# schematic_revision_1.net
KiCad netlist of a schematic drawn in EAGLE
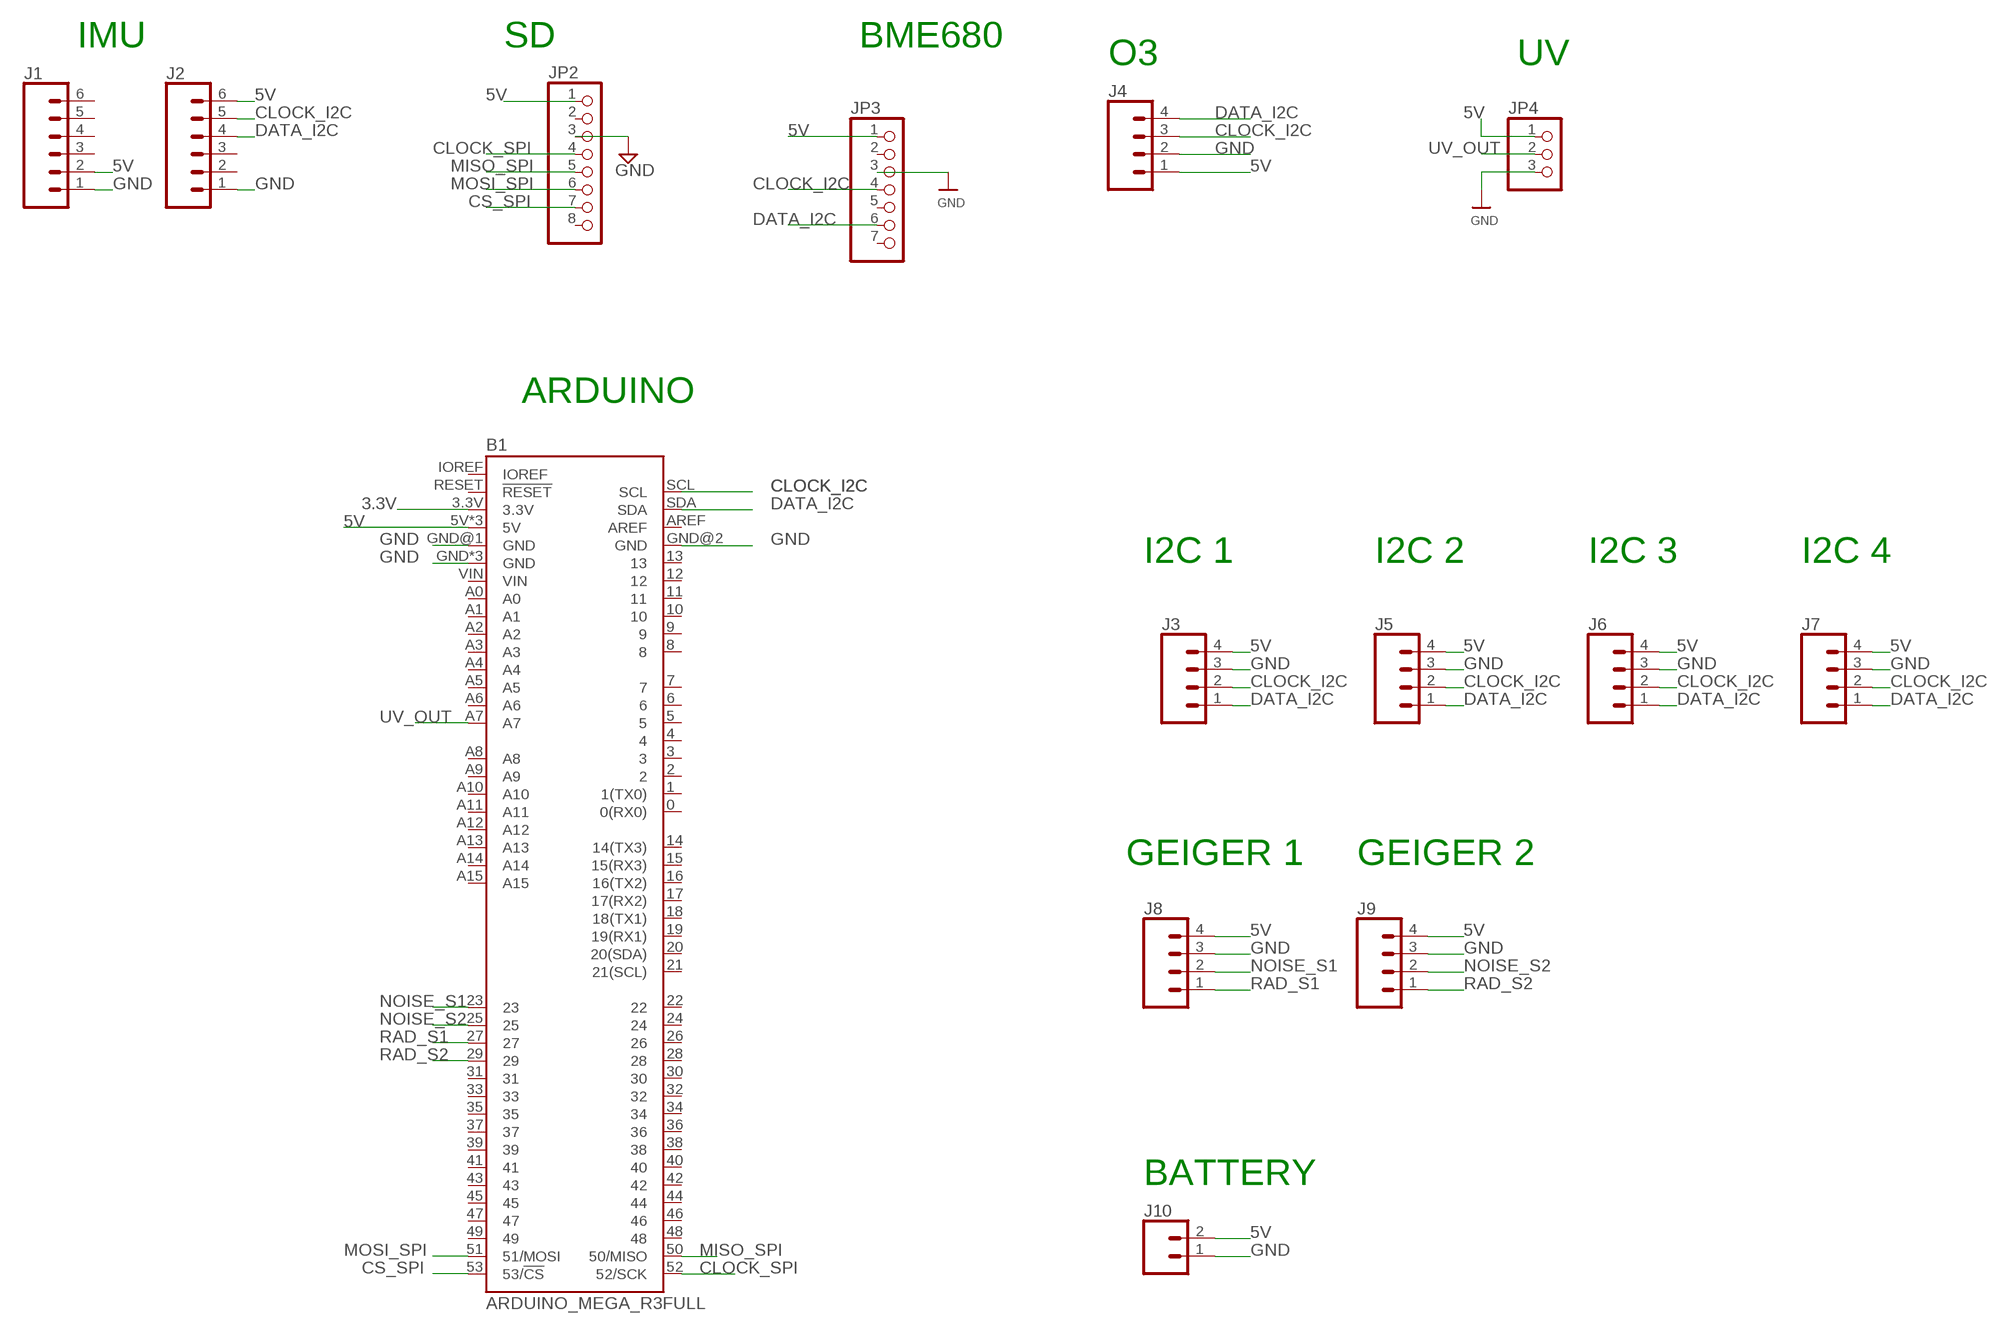
[diagram p0: schematic, sheet 1, part 1 of 2]
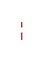
[diagram p1: schematic, sheet 1, part 2 of 2]

(export (version "E")
  (design (tool "Eeschema 10.0.6"))
  (components
    (comp (ref "B1")
      (value "ARDUINO_MEGA_R3FULL")
      (footprint "eagle-import:ARDUINO_MEGA_NO_SILK")
      (libsource (lib "eagle-import") (part "ARDUINO_MEGA_R3FULL"))
    )
    (comp (ref "J1")
      (value "CONN_06NO_SILK_NO_POP")
      (footprint "eagle-import:1X06_NO_SILK")
      (libsource (lib "eagle-import") (part "CONN_06NO_SILK_NO_POP"))
    )
    (comp (ref "J2")
      (value "CONN_06NO_SILK_NO_POP")
      (footprint "eagle-import:1X06_NO_SILK")
      (libsource (lib "eagle-import") (part "CONN_06NO_SILK_NO_POP"))
    )
    (comp (ref "J3")
      (value "CONN_04PTH")
      (footprint "eagle-import:1X04")
      (libsource (lib "eagle-import") (part "CONN_04PTH"))
    )
    (comp (ref "J4")
      (value "CONN_04LOCK")
      (footprint "eagle-import:1X04_LOCK")
      (libsource (lib "eagle-import") (part "CONN_04LOCK"))
    )
    (comp (ref "J5")
      (value "CONN_04PTH")
      (footprint "eagle-import:1X04")
      (libsource (lib "eagle-import") (part "CONN_04PTH"))
    )
    (comp (ref "J6")
      (value "CONN_04PTH")
      (footprint "eagle-import:1X04")
      (libsource (lib "eagle-import") (part "CONN_04PTH"))
    )
    (comp (ref "J7")
      (value "CONN_04PTH")
      (footprint "eagle-import:1X04")
      (libsource (lib "eagle-import") (part "CONN_04PTH"))
    )
    (comp (ref "J8")
      (value "CONN_04PTH")
      (footprint "eagle-import:1X04")
      (libsource (lib "eagle-import") (part "CONN_04PTH"))
    )
    (comp (ref "J9")
      (value "CONN_04PTH")
      (footprint "eagle-import:1X04")
      (libsource (lib "eagle-import") (part "CONN_04PTH"))
    )
    (comp (ref "J10")
      (value "CONN_02")
      (footprint "eagle-import:1X02")
      (libsource (lib "eagle-import") (part "CONN_02"))
    )
    (comp (ref "JP2")
      (value "PINHD-1X8BIG")
      (footprint "eagle-import:1X08-BIG")
      (libsource (lib "eagle-import") (part "PINHD-1X8BIG"))
    )
    (comp (ref "JP3")
      (value "HEADER-1X770MIL")
      (footprint "eagle-import:1X07_ROUND_70")
      (libsource (lib "eagle-import") (part "HEADER-1X770MIL"))
    )
    (comp (ref "JP4")
      (value "PINHD-1X3CB")
      (footprint "eagle-import:1X03-CLEANBIG")
      (libsource (lib "eagle-import") (part "PINHD-1X3CB"))
    )
  )
  (nets
    (net (code "1") (name "/3.3V") (class "Default")
      (node (ref "B1") (pin "3.3V") (pinfunction "3.3V_3.3V") (pintype "bidirectional"))
    )
    (net (code "2") (name "/5V") (class "Default")
      (node (ref "B1") (pin "5V") (pinfunction "5V_5V") (pintype "bidirectional"))
      (node (ref "B1") (pin "5V@1") (pinfunction "5V_5V@1") (pintype "bidirectional"))
      (node (ref "B1") (pin "5V@2") (pinfunction "5V_5V@2") (pintype "bidirectional"))
      (node (ref "J1") (pin "2") (pinfunction "2_2") (pintype "passive"))
      (node (ref "J10") (pin "2") (pinfunction "2_2") (pintype "passive"))
      (node (ref "J2") (pin "6") (pinfunction "6_6") (pintype "passive"))
      (node (ref "J3") (pin "4") (pinfunction "4_4") (pintype "passive"))
      (node (ref "J4") (pin "1") (pinfunction "1_1") (pintype "passive"))
      (node (ref "J5") (pin "4") (pinfunction "4_4") (pintype "passive"))
      (node (ref "J6") (pin "4") (pinfunction "4_4") (pintype "passive"))
      (node (ref "J7") (pin "4") (pinfunction "4_4") (pintype "passive"))
      (node (ref "J8") (pin "4") (pinfunction "4_4") (pintype "passive"))
      (node (ref "J9") (pin "4") (pinfunction "4_4") (pintype "passive"))
      (node (ref "JP2") (pin "1") (pinfunction "1_1") (pintype "passive"))
      (node (ref "JP3") (pin "1") (pinfunction "1_1") (pintype "passive"))
      (node (ref "JP4") (pin "1") (pinfunction "1_1") (pintype "passive"))
    )
    (net (code "3") (name "/CLOCK_I2C") (class "Default")
      (node (ref "B1") (pin "SCL") (pinfunction "SCL_SCL") (pintype "bidirectional"))
      (node (ref "J2") (pin "5") (pinfunction "5_5") (pintype "passive"))
      (node (ref "J3") (pin "2") (pinfunction "2_2") (pintype "passive"))
      (node (ref "J4") (pin "3") (pinfunction "3_3") (pintype "passive"))
      (node (ref "J5") (pin "2") (pinfunction "2_2") (pintype "passive"))
      (node (ref "J6") (pin "2") (pinfunction "2_2") (pintype "passive"))
      (node (ref "J7") (pin "2") (pinfunction "2_2") (pintype "passive"))
      (node (ref "JP3") (pin "4") (pinfunction "4_4") (pintype "passive"))
    )
    (net (code "4") (name "/CLOCK_SPI") (class "Default")
      (node (ref "B1") (pin "52") (pinfunction "52/SCK_52") (pintype "bidirectional"))
      (node (ref "JP2") (pin "4") (pinfunction "4_4") (pintype "passive"))
    )
    (net (code "5") (name "/CS_SPI") (class "Default")
      (node (ref "B1") (pin "53") (pinfunction "53/~{CS}_53") (pintype "bidirectional"))
      (node (ref "JP2") (pin "7") (pinfunction "7_7") (pintype "passive"))
    )
    (net (code "6") (name "/DATA_I2C") (class "Default")
      (node (ref "B1") (pin "SDA") (pinfunction "SDA_SDA") (pintype "bidirectional"))
      (node (ref "J2") (pin "4") (pinfunction "4_4") (pintype "passive"))
      (node (ref "J3") (pin "1") (pinfunction "1_1") (pintype "passive"))
      (node (ref "J4") (pin "4") (pinfunction "4_4") (pintype "passive"))
      (node (ref "J5") (pin "1") (pinfunction "1_1") (pintype "passive"))
      (node (ref "J6") (pin "1") (pinfunction "1_1") (pintype "passive"))
      (node (ref "J7") (pin "1") (pinfunction "1_1") (pintype "passive"))
      (node (ref "JP3") (pin "6") (pinfunction "6_6") (pintype "passive"))
    )
    (net (code "7") (name "/MISO_SPI") (class "Default")
      (node (ref "B1") (pin "50") (pinfunction "50/MISO_50") (pintype "bidirectional"))
      (node (ref "JP2") (pin "5") (pinfunction "5_5") (pintype "passive"))
    )
    (net (code "8") (name "/MOSI_SPI") (class "Default")
      (node (ref "B1") (pin "51") (pinfunction "51/MOSI_51") (pintype "bidirectional"))
      (node (ref "JP2") (pin "6") (pinfunction "6_6") (pintype "passive"))
    )
    (net (code "9") (name "/NOISE_S1") (class "Default")
      (node (ref "B1") (pin "23") (pinfunction "23_23") (pintype "bidirectional"))
      (node (ref "J8") (pin "2") (pinfunction "2_2") (pintype "passive"))
    )
    (net (code "10") (name "/NOISE_S2") (class "Default")
      (node (ref "B1") (pin "25") (pinfunction "25_25") (pintype "bidirectional"))
      (node (ref "J9") (pin "2") (pinfunction "2_2") (pintype "passive"))
    )
    (net (code "11") (name "/RAD_S1") (class "Default")
      (node (ref "B1") (pin "27") (pinfunction "27_27") (pintype "bidirectional"))
      (node (ref "J8") (pin "1") (pinfunction "1_1") (pintype "passive"))
    )
    (net (code "12") (name "/RAD_S2") (class "Default")
      (node (ref "B1") (pin "29") (pinfunction "29_29") (pintype "bidirectional"))
      (node (ref "J9") (pin "1") (pinfunction "1_1") (pintype "passive"))
    )
    (net (code "13") (name "/UV_OUT") (class "Default")
      (node (ref "B1") (pin "A7") (pinfunction "A7_A7") (pintype "bidirectional"))
      (node (ref "JP4") (pin "2") (pinfunction "2_2") (pintype "passive"))
    )
    (net (code "14") (name "GND") (class "Default")
      (node (ref "B1") (pin "GND") (pinfunction "GND_GND") (pintype "bidirectional"))
      (node (ref "B1") (pin "GND@1") (pinfunction "GND_GND@1") (pintype "bidirectional"))
      (node (ref "B1") (pin "GND@2") (pinfunction "GND_GND@2") (pintype "bidirectional"))
      (node (ref "B1") (pin "GND@3") (pinfunction "GND_GND@3") (pintype "bidirectional"))
      (node (ref "B1") (pin "GND@4") (pinfunction "GND_GND@4") (pintype "bidirectional"))
      (node (ref "J1") (pin "1") (pinfunction "1_1") (pintype "passive"))
      (node (ref "J10") (pin "1") (pinfunction "1_1") (pintype "passive"))
      (node (ref "J2") (pin "1") (pinfunction "1_1") (pintype "passive"))
      (node (ref "J3") (pin "3") (pinfunction "3_3") (pintype "passive"))
      (node (ref "J4") (pin "2") (pinfunction "2_2") (pintype "passive"))
      (node (ref "J5") (pin "3") (pinfunction "3_3") (pintype "passive"))
      (node (ref "J6") (pin "3") (pinfunction "3_3") (pintype "passive"))
      (node (ref "J7") (pin "3") (pinfunction "3_3") (pintype "passive"))
      (node (ref "J8") (pin "3") (pinfunction "3_3") (pintype "passive"))
      (node (ref "J9") (pin "3") (pinfunction "3_3") (pintype "passive"))
      (node (ref "JP2") (pin "3") (pinfunction "3_3") (pintype "passive"))
      (node (ref "JP3") (pin "3") (pinfunction "3_3") (pintype "passive"))
      (node (ref "JP4") (pin "3") (pinfunction "3_3") (pintype "passive"))
    )
    (net (code "15") (name "unconnected-(B1-0(RX0)-Pad0)") (class "Default")
      (node (ref "B1") (pin "0") (pinfunction "0(RX0)_0") (pintype "bidirectional"))
    )
    (net (code "16") (name "unconnected-(B1-1(TX0)-Pad1)") (class "Default")
      (node (ref "B1") (pin "1") (pinfunction "1(TX0)_1") (pintype "bidirectional"))
    )
    (net (code "17") (name "unconnected-(B1-14(TX3)-Pad14)") (class "Default")
      (node (ref "B1") (pin "14") (pinfunction "14(TX3)_14") (pintype "bidirectional"))
    )
    (net (code "18") (name "unconnected-(B1-15(RX3)-Pad15)") (class "Default")
      (node (ref "B1") (pin "15") (pinfunction "15(RX3)_15") (pintype "bidirectional"))
    )
    (net (code "19") (name "unconnected-(B1-16(TX2)-Pad16)") (class "Default")
      (node (ref "B1") (pin "16") (pinfunction "16(TX2)_16") (pintype "bidirectional"))
    )
    (net (code "20") (name "unconnected-(B1-17(RX2)-Pad17)") (class "Default")
      (node (ref "B1") (pin "17") (pinfunction "17(RX2)_17") (pintype "bidirectional"))
    )
    (net (code "21") (name "unconnected-(B1-18(TX1)-Pad18)") (class "Default")
      (node (ref "B1") (pin "18") (pinfunction "18(TX1)_18") (pintype "bidirectional"))
    )
    (net (code "22") (name "unconnected-(B1-19(RX1)-Pad19)") (class "Default")
      (node (ref "B1") (pin "19") (pinfunction "19(RX1)_19") (pintype "bidirectional"))
    )
    (net (code "23") (name "unconnected-(B1-20(SDA)-Pad20)") (class "Default")
      (node (ref "B1") (pin "20") (pinfunction "20(SDA)_20") (pintype "bidirectional"))
    )
    (net (code "24") (name "unconnected-(B1-21(SCL)-Pad21)") (class "Default")
      (node (ref "B1") (pin "21") (pinfunction "21(SCL)_21") (pintype "bidirectional"))
    )
    (net (code "25") (name "unconnected-(B1-Pad2)") (class "Default")
      (node (ref "B1") (pin "2") (pinfunction "2_2") (pintype "bidirectional"))
    )
    (net (code "26") (name "unconnected-(B1-Pad3)") (class "Default")
      (node (ref "B1") (pin "3") (pinfunction "3_3") (pintype "bidirectional"))
    )
    (net (code "27") (name "unconnected-(B1-Pad4)") (class "Default")
      (node (ref "B1") (pin "4") (pinfunction "4_4") (pintype "bidirectional"))
    )
    (net (code "28") (name "unconnected-(B1-Pad5)") (class "Default")
      (node (ref "B1") (pin "5") (pinfunction "5_5") (pintype "bidirectional"))
    )
    (net (code "29") (name "unconnected-(B1-Pad6)") (class "Default")
      (node (ref "B1") (pin "6") (pinfunction "6_6") (pintype "bidirectional"))
    )
    (net (code "30") (name "unconnected-(B1-Pad7)") (class "Default")
      (node (ref "B1") (pin "7") (pinfunction "7_7") (pintype "bidirectional"))
    )
    (net (code "31") (name "unconnected-(B1-Pad8)") (class "Default")
      (node (ref "B1") (pin "8") (pinfunction "8_8") (pintype "bidirectional"))
    )
    (net (code "32") (name "unconnected-(B1-Pad9)") (class "Default")
      (node (ref "B1") (pin "9") (pinfunction "9_9") (pintype "bidirectional"))
    )
    (net (code "33") (name "unconnected-(B1-Pad10)") (class "Default")
      (node (ref "B1") (pin "10") (pinfunction "10_10") (pintype "bidirectional"))
    )
    (net (code "34") (name "unconnected-(B1-Pad11)") (class "Default")
      (node (ref "B1") (pin "11") (pinfunction "11_11") (pintype "bidirectional"))
    )
    (net (code "35") (name "unconnected-(B1-Pad12)") (class "Default")
      (node (ref "B1") (pin "12") (pinfunction "12_12") (pintype "bidirectional"))
    )
    (net (code "36") (name "unconnected-(B1-Pad13)") (class "Default")
      (node (ref "B1") (pin "13") (pinfunction "13_13") (pintype "bidirectional"))
    )
    (net (code "37") (name "unconnected-(B1-Pad22)") (class "Default")
      (node (ref "B1") (pin "22") (pinfunction "22_22") (pintype "bidirectional"))
    )
    (net (code "38") (name "unconnected-(B1-Pad24)") (class "Default")
      (node (ref "B1") (pin "24") (pinfunction "24_24") (pintype "bidirectional"))
    )
    (net (code "39") (name "unconnected-(B1-Pad26)") (class "Default")
      (node (ref "B1") (pin "26") (pinfunction "26_26") (pintype "bidirectional"))
    )
    (net (code "40") (name "unconnected-(B1-Pad28)") (class "Default")
      (node (ref "B1") (pin "28") (pinfunction "28_28") (pintype "bidirectional"))
    )
    (net (code "41") (name "unconnected-(B1-Pad30)") (class "Default")
      (node (ref "B1") (pin "30") (pinfunction "30_30") (pintype "bidirectional"))
    )
    (net (code "42") (name "unconnected-(B1-Pad31)") (class "Default")
      (node (ref "B1") (pin "31") (pinfunction "31_31") (pintype "bidirectional"))
    )
    (net (code "43") (name "unconnected-(B1-Pad32)") (class "Default")
      (node (ref "B1") (pin "32") (pinfunction "32_32") (pintype "bidirectional"))
    )
    (net (code "44") (name "unconnected-(B1-Pad33)") (class "Default")
      (node (ref "B1") (pin "33") (pinfunction "33_33") (pintype "bidirectional"))
    )
    (net (code "45") (name "unconnected-(B1-Pad34)") (class "Default")
      (node (ref "B1") (pin "34") (pinfunction "34_34") (pintype "bidirectional"))
    )
    (net (code "46") (name "unconnected-(B1-Pad35)") (class "Default")
      (node (ref "B1") (pin "35") (pinfunction "35_35") (pintype "bidirectional"))
    )
    (net (code "47") (name "unconnected-(B1-Pad36)") (class "Default")
      (node (ref "B1") (pin "36") (pinfunction "36_36") (pintype "bidirectional"))
    )
    (net (code "48") (name "unconnected-(B1-Pad37)") (class "Default")
      (node (ref "B1") (pin "37") (pinfunction "37_37") (pintype "bidirectional"))
    )
    (net (code "49") (name "unconnected-(B1-Pad38)") (class "Default")
      (node (ref "B1") (pin "38") (pinfunction "38_38") (pintype "bidirectional"))
    )
    (net (code "50") (name "unconnected-(B1-Pad39)") (class "Default")
      (node (ref "B1") (pin "39") (pinfunction "39_39") (pintype "bidirectional"))
    )
    (net (code "51") (name "unconnected-(B1-Pad40)") (class "Default")
      (node (ref "B1") (pin "40") (pinfunction "40_40") (pintype "bidirectional"))
    )
    (net (code "52") (name "unconnected-(B1-Pad41)") (class "Default")
      (node (ref "B1") (pin "41") (pinfunction "41_41") (pintype "bidirectional"))
    )
    (net (code "53") (name "unconnected-(B1-Pad42)") (class "Default")
      (node (ref "B1") (pin "42") (pinfunction "42_42") (pintype "bidirectional"))
    )
    (net (code "54") (name "unconnected-(B1-Pad43)") (class "Default")
      (node (ref "B1") (pin "43") (pinfunction "43_43") (pintype "bidirectional"))
    )
    (net (code "55") (name "unconnected-(B1-Pad44)") (class "Default")
      (node (ref "B1") (pin "44") (pinfunction "44_44") (pintype "bidirectional"))
    )
    (net (code "56") (name "unconnected-(B1-Pad45)") (class "Default")
      (node (ref "B1") (pin "45") (pinfunction "45_45") (pintype "bidirectional"))
    )
    (net (code "57") (name "unconnected-(B1-Pad46)") (class "Default")
      (node (ref "B1") (pin "46") (pinfunction "46_46") (pintype "bidirectional"))
    )
    (net (code "58") (name "unconnected-(B1-Pad47)") (class "Default")
      (node (ref "B1") (pin "47") (pinfunction "47_47") (pintype "bidirectional"))
    )
    (net (code "59") (name "unconnected-(B1-Pad48)") (class "Default")
      (node (ref "B1") (pin "48") (pinfunction "48_48") (pintype "bidirectional"))
    )
    (net (code "60") (name "unconnected-(B1-Pad49)") (class "Default")
      (node (ref "B1") (pin "49") (pinfunction "49_49") (pintype "bidirectional"))
    )
    (net (code "61") (name "unconnected-(B1-PadA0)") (class "Default")
      (node (ref "B1") (pin "A0") (pinfunction "A0_A0") (pintype "bidirectional"))
    )
    (net (code "62") (name "unconnected-(B1-PadA1)") (class "Default")
      (node (ref "B1") (pin "A1") (pinfunction "A1_A1") (pintype "bidirectional"))
    )
    (net (code "63") (name "unconnected-(B1-PadA2)") (class "Default")
      (node (ref "B1") (pin "A2") (pinfunction "A2_A2") (pintype "bidirectional"))
    )
    (net (code "64") (name "unconnected-(B1-PadA3)") (class "Default")
      (node (ref "B1") (pin "A3") (pinfunction "A3_A3") (pintype "bidirectional"))
    )
    (net (code "65") (name "unconnected-(B1-PadA4)") (class "Default")
      (node (ref "B1") (pin "A4") (pinfunction "A4_A4") (pintype "bidirectional"))
    )
    (net (code "66") (name "unconnected-(B1-PadA5)") (class "Default")
      (node (ref "B1") (pin "A5") (pinfunction "A5_A5") (pintype "bidirectional"))
    )
    (net (code "67") (name "unconnected-(B1-PadA6)") (class "Default")
      (node (ref "B1") (pin "A6") (pinfunction "A6_A6") (pintype "bidirectional"))
    )
    (net (code "68") (name "unconnected-(B1-PadA8)") (class "Default")
      (node (ref "B1") (pin "A8") (pinfunction "A8_A8") (pintype "bidirectional"))
    )
    (net (code "69") (name "unconnected-(B1-PadA9)") (class "Default")
      (node (ref "B1") (pin "A9") (pinfunction "A9_A9") (pintype "bidirectional"))
    )
    (net (code "70") (name "unconnected-(B1-PadA10)") (class "Default")
      (node (ref "B1") (pin "A10") (pinfunction "A10_A10") (pintype "bidirectional"))
    )
    (net (code "71") (name "unconnected-(B1-PadA11)") (class "Default")
      (node (ref "B1") (pin "A11") (pinfunction "A11_A11") (pintype "bidirectional"))
    )
    (net (code "72") (name "unconnected-(B1-PadA12)") (class "Default")
      (node (ref "B1") (pin "A12") (pinfunction "A12_A12") (pintype "bidirectional"))
    )
    (net (code "73") (name "unconnected-(B1-PadA13)") (class "Default")
      (node (ref "B1") (pin "A13") (pinfunction "A13_A13") (pintype "bidirectional"))
    )
    (net (code "74") (name "unconnected-(B1-PadA14)") (class "Default")
      (node (ref "B1") (pin "A14") (pinfunction "A14_A14") (pintype "bidirectional"))
    )
    (net (code "75") (name "unconnected-(B1-PadA15)") (class "Default")
      (node (ref "B1") (pin "A15") (pinfunction "A15_A15") (pintype "bidirectional"))
    )
    (net (code "76") (name "unconnected-(B1-PadAREF)") (class "Default")
      (node (ref "B1") (pin "AREF") (pinfunction "AREF_AREF") (pintype "bidirectional"))
    )
    (net (code "77") (name "unconnected-(B1-PadIOREF)") (class "Default")
      (node (ref "B1") (pin "IOREF") (pinfunction "IOREF_IOREF") (pintype "bidirectional"))
    )
    (net (code "78") (name "unconnected-(B1-PadVIN)") (class "Default")
      (node (ref "B1") (pin "VIN") (pinfunction "VIN_VIN") (pintype "bidirectional"))
    )
    (net (code "79") (name "unconnected-(B1-~{RESET}-PadRESET)") (class "Default")
      (node (ref "B1") (pin "RESET") (pinfunction "~{RESET}_RESET") (pintype "bidirectional"))
    )
    (net (code "80") (name "unconnected-(J1-Pad3)") (class "Default")
      (node (ref "J1") (pin "3") (pinfunction "3_3") (pintype "passive"))
    )
    (net (code "81") (name "unconnected-(J1-Pad4)") (class "Default")
      (node (ref "J1") (pin "4") (pinfunction "4_4") (pintype "passive"))
    )
    (net (code "82") (name "unconnected-(J1-Pad5)") (class "Default")
      (node (ref "J1") (pin "5") (pinfunction "5_5") (pintype "passive"))
    )
    (net (code "83") (name "unconnected-(J1-Pad6)") (class "Default")
      (node (ref "J1") (pin "6") (pinfunction "6_6") (pintype "passive"))
    )
    (net (code "84") (name "unconnected-(J2-Pad2)") (class "Default")
      (node (ref "J2") (pin "2") (pinfunction "2_2") (pintype "passive"))
    )
    (net (code "85") (name "unconnected-(J2-Pad3)") (class "Default")
      (node (ref "J2") (pin "3") (pinfunction "3_3") (pintype "passive"))
    )
    (net (code "86") (name "unconnected-(JP2-Pad2)") (class "Default")
      (node (ref "JP2") (pin "2") (pinfunction "2_2") (pintype "passive"))
    )
    (net (code "87") (name "unconnected-(JP2-Pad8)") (class "Default")
      (node (ref "JP2") (pin "8") (pinfunction "8_8") (pintype "passive"))
    )
    (net (code "88") (name "unconnected-(JP3-Pad2)") (class "Default")
      (node (ref "JP3") (pin "2") (pinfunction "2_2") (pintype "passive"))
    )
    (net (code "89") (name "unconnected-(JP3-Pad5)") (class "Default")
      (node (ref "JP3") (pin "5") (pinfunction "5_5") (pintype "passive"))
    )
    (net (code "90") (name "unconnected-(JP3-Pad7)") (class "Default")
      (node (ref "JP3") (pin "7") (pinfunction "7_7") (pintype "passive"))
    )
  )
)
